# 01_MCU.net
KiCad netlist of a schematic drawn in Altium Designer
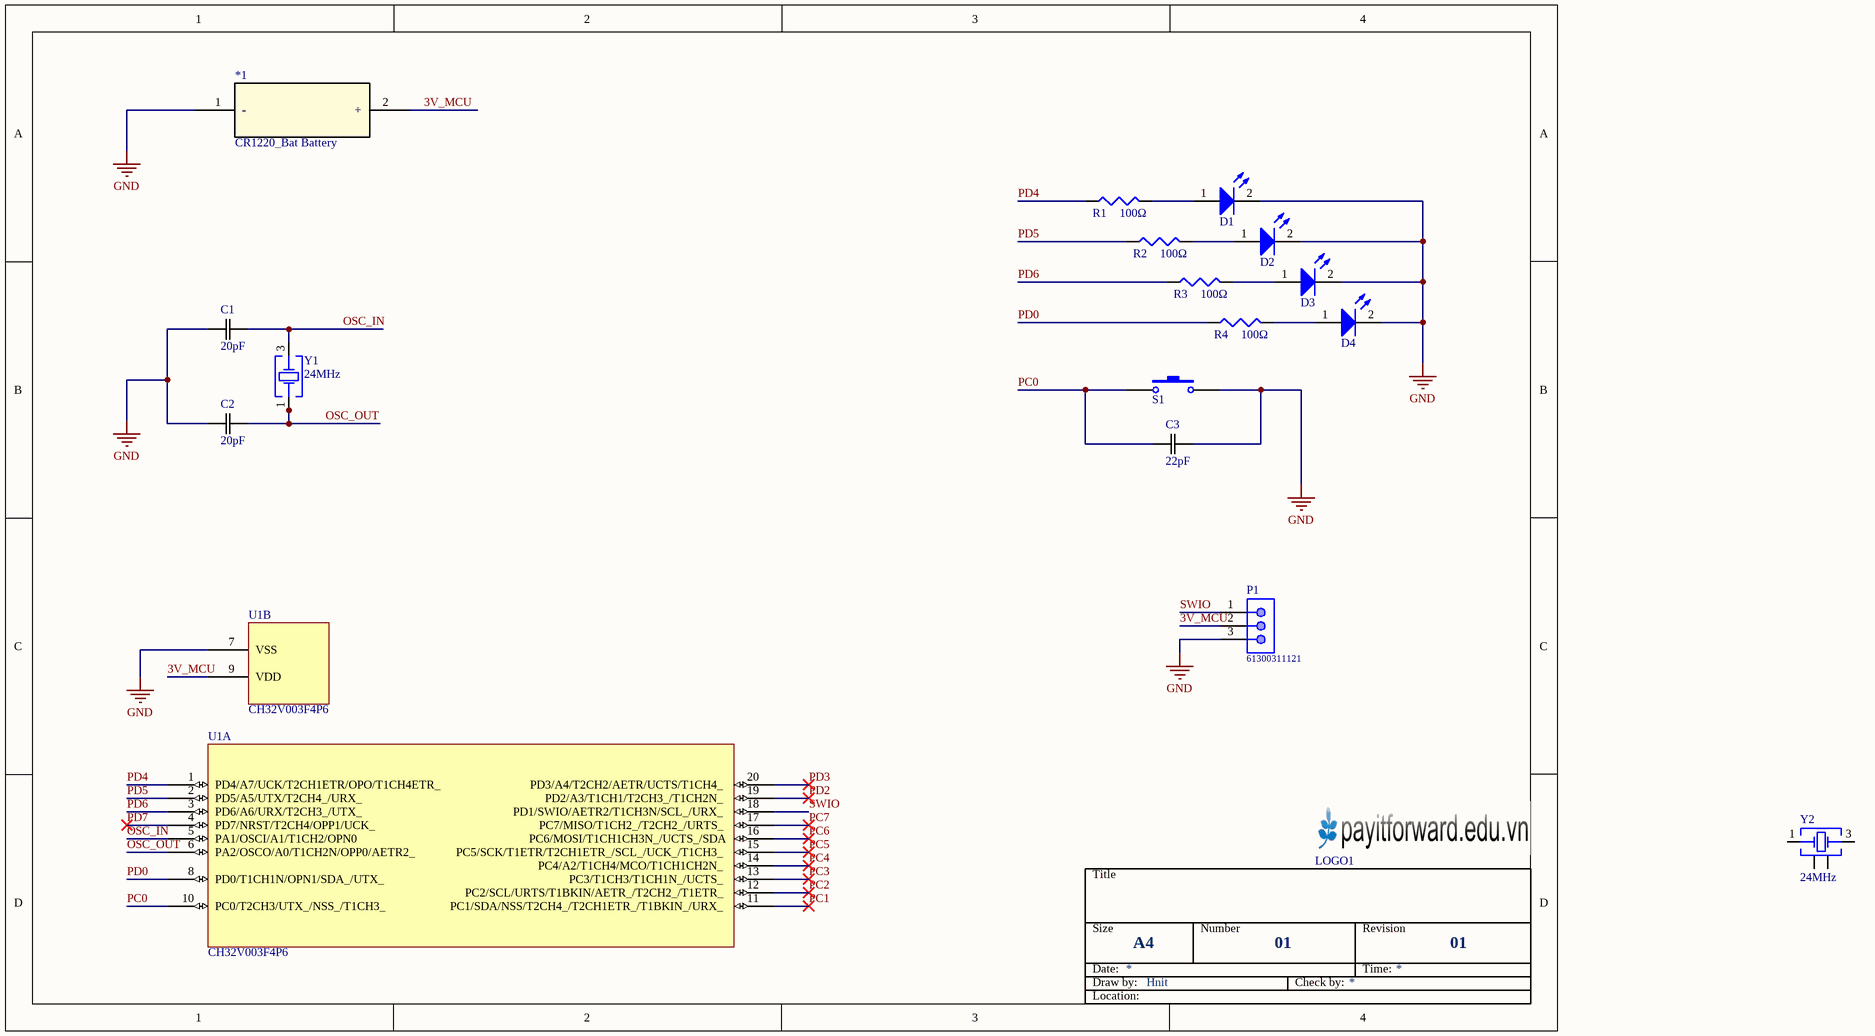
[diagram p0: 01_MCU.SchDoc]

(export (version "E")
  (design (tool "Eeschema 10.0.6"))
  (components
    (comp (ref "*1")
      (value "CR1220_Bat Battery")
      (footprint "CR1220_Bat Battery")
      (libsource (lib "IntegratedLibrary_Hnit") (part "CR1220_Bat Battery"))
    )
    (comp (ref "C1")
      (value "20pF")
      (footprint "CAPC17595_87N_KEM_0603")
      (description "No Description Available")
      (fields
        (field (name "MANUFACTURER_PART_NUMBER") "C1206C104K5RACTU")
        (field (name "COPYRIGHT") "Copyright (C) 2023 Ultra Librarian. All rights reserved.")
      )
      (libsource (lib "IntegratedLibrary_Hnit") (part "Capacitor_SMD"))
    )
    (comp (ref "C2")
      (value "20pF")
      (footprint "CAPC17595_87N_KEM_0603")
      (description "No Description Available")
      (fields
        (field (name "MANUFACTURER_PART_NUMBER") "C1206C104K5RACTU")
        (field (name "COPYRIGHT") "Copyright (C) 2023 Ultra Librarian. All rights reserved.")
      )
      (libsource (lib "IntegratedLibrary_Hnit") (part "Capacitor_SMD"))
    )
    (comp (ref "C3")
      (value "22pF")
      (footprint "CAPC17595_87N_KEM_0603")
      (description "No Description Available")
      (fields
        (field (name "MANUFACTURER_PART_NUMBER") "C1206C104K5RACTU")
        (field (name "COPYRIGHT") "Copyright (C) 2023 Ultra Librarian. All rights reserved.")
      )
      (libsource (lib "IntegratedLibrary_Hnit") (part "Capacitor_SMD"))
    )
    (comp (ref "D1")
      (value "Color ? , 3.2V, 140°")
      (footprint "WL-SMCW_0603_150060xx75003")
      (description "WL-SMCW Mono-color Chip LED Waterclear, size ?, color ?, 3.2V, 140°")
      (fields
        (field (name "MANUFACTURER PART NUMBER") "150060BS75003")
        (field (name "MANUFACTURER") "Wurth Elektronik")
      )
      (libsource (lib "IntegratedLibrary_Hnit") (part "LED_smd"))
    )
    (comp (ref "D2")
      (value "Color ? , 3.2V, 140°")
      (footprint "WL-SMCW_0603_150060xx75003")
      (description "WL-SMCW Mono-color Chip LED Waterclear, size ?, color ?, 3.2V, 140°")
      (fields
        (field (name "MANUFACTURER PART NUMBER") "150060BS75003")
        (field (name "MANUFACTURER") "Wurth Elektronik")
      )
      (libsource (lib "IntegratedLibrary_Hnit") (part "LED_smd"))
    )
    (comp (ref "D3")
      (value "Color ? , 3.2V, 140°")
      (footprint "WL-SMCW_0603_150060xx75003")
      (description "WL-SMCW Mono-color Chip LED Waterclear, size ?, color ?, 3.2V, 140°")
      (fields
        (field (name "MANUFACTURER PART NUMBER") "150060BS75003")
        (field (name "MANUFACTURER") "Wurth Elektronik")
      )
      (libsource (lib "IntegratedLibrary_Hnit") (part "LED_smd"))
    )
    (comp (ref "D4")
      (value "Color ? , 3.2V, 140°")
      (footprint "WL-SMCW_0603_150060xx75003")
      (description "WL-SMCW Mono-color Chip LED Waterclear, size ?, color ?, 3.2V, 140°")
      (fields
        (field (name "MANUFACTURER PART NUMBER") "150060BS75003")
        (field (name "MANUFACTURER") "Wurth Elektronik")
      )
      (libsource (lib "IntegratedLibrary_Hnit") (part "LED_smd"))
    )
    (comp (ref "LOGO1")
      (value "LOGO PIF")
      (footprint "PIF LOGO BIG TOP")
      (libsource (lib "PIF_Library") (part "LOGO PIF"))
    )
    (comp (ref "P1")
      (value "61300311121")
      (footprint "61300311121")
      (description "WR-PHD Pin Header, THT, pitch 2.54mm, Single Row, Vertical, 3p")
      (fields (field (name "MANUFACTURER") "Wurth Elektronik"))
      (libsource (lib "Altium_WR-PHD (rev20a)") (part "61300311121"))
    )
    (comp (ref "R1")
      (value "100Ω")
      (footprint "WRIS-PSMB_0603_L1.6W0.8H0.3 - duplicate")
      (description "WRIS-PSMC Metal Plate Resistor, SMT, size 2512, 2W, 5mΩ, +/-1%")
      (fields
        (field (name "MANUFACTURER PART NUMBER") "580070763005")
        (field (name "MANUFACTURER") "Wurth Elektronik")
      )
      (libsource (lib "IntegratedLibrary_Hnit") (part "Resistor_SMD"))
    )
    (comp (ref "R2")
      (value "100Ω")
      (footprint "WRIS-PSMB_0603_L1.6W0.8H0.3 - duplicate")
      (description "WRIS-PSMC Metal Plate Resistor, SMT, size 2512, 2W, 5mΩ, +/-1%")
      (fields
        (field (name "MANUFACTURER PART NUMBER") "580070763005")
        (field (name "MANUFACTURER") "Wurth Elektronik")
      )
      (libsource (lib "IntegratedLibrary_Hnit") (part "Resistor_SMD"))
    )
    (comp (ref "R3")
      (value "100Ω")
      (footprint "WRIS-PSMB_0603_L1.6W0.8H0.3 - duplicate")
      (description "WRIS-PSMC Metal Plate Resistor, SMT, size 2512, 2W, 5mΩ, +/-1%")
      (fields
        (field (name "MANUFACTURER PART NUMBER") "580070763005")
        (field (name "MANUFACTURER") "Wurth Elektronik")
      )
      (libsource (lib "IntegratedLibrary_Hnit") (part "Resistor_SMD"))
    )
    (comp (ref "R4")
      (value "100Ω")
      (footprint "WRIS-PSMB_0603_L1.6W0.8H0.3 - duplicate")
      (description "WRIS-PSMC Metal Plate Resistor, SMT, size 2512, 2W, 5mΩ, +/-1%")
      (fields
        (field (name "MANUFACTURER PART NUMBER") "580070763005")
        (field (name "MANUFACTURER") "Wurth Elektronik")
      )
      (libsource (lib "IntegratedLibrary_Hnit") (part "Resistor_SMD"))
    )
    (comp (ref "S1")
      (value "Tact SW - 2Pin")
      (footprint "SW-SMD")
      (description "Switch button 2 pin")
      (libsource (lib "IntegratedLibrary_Hnit") (part "Tact SW - 2Pin"))
    )
    (comp (ref "U1")
      (value "CH32V003F4P6")
      (footprint "TSOP20_CH32V003")
      (fields
        (field (name "VENDOR CONFIGURATION WORD STORAGE, FACTORY-CURED AND UNMODIFIABLE BY USERS") "64B")
      )
      (libsource (lib "IntegratedLibrary_Hnit") (part "CH32V003F4P6"))
    )
    (comp (ref "Y1")
      (value "24MHz")
      (footprint "WE-XTAL_CFPX-5032_2Pin")
      (description "WE-XTAL Quartz Crystal, SMT, CFPX-104, 24MHz, +/-50ppm")
      (fields
        (field (name "MANUFACTURER PART NUMBER") "830032817")
        (field (name "MANUFACTURER") "Wurth Elektronik")
      )
      (libsource (lib "IntegratedLibrary_Hnit") (part "XTAL_SMD"))
    )
    (comp (ref "Y2")
      (value "24MHz")
      (footprint "WE-XTAL_CFPX-104")
      (description "WE-XTAL Quartz Crystal, SMT, CFPX-104, 24MHz, +/-50ppm")
      (fields
        (field (name "MANUFACTURER PART NUMBER") "830032817")
        (field (name "MANUFACTURER") "Wurth Elektronik")
      )
      (libsource (lib "") (part "XTAL_SMD_1"))
    )
  )
  (nets
    (net (code "1") (name "/3V_MCU") (class "Default")
      (node (ref "*1") (pin "2") (pinfunction "+_2") (pintype "passive"))
      (node (ref "P1") (pin "2") (pinfunction "2_2") (pintype "passive"))
      (node (ref "U1") (pin "9") (pinfunction "VDD_9") (pintype "power_in"))
    )
    (net (code "2") (name "/OSC_IN") (class "Default")
      (node (ref "C1") (pin "2") (pinfunction "2_2") (pintype "passive"))
      (node (ref "U1") (pin "5") (pinfunction "PA1/OSCI/A1/T1CH2/OPN0_5") (pintype "bidirectional"))
      (node (ref "Y1") (pin "3") (pinfunction "Crystal_3") (pintype "passive"))
    )
    (net (code "3") (name "/OSC_OUT") (class "Default")
      (node (ref "C2") (pin "2") (pinfunction "2_2") (pintype "passive"))
      (node (ref "U1") (pin "6") (pinfunction "PA2/OSCO/A0/T1CH2N/OPP0/AETR2__6") (pintype "bidirectional"))
      (node (ref "Y1") (pin "1") (pinfunction "Crystal_1") (pintype "passive"))
    )
    (net (code "4") (name "/PC0") (class "Default")
      (node (ref "C3") (pin "1") (pinfunction "1_1") (pintype "passive"))
      (node (ref "S1") (pin "1") (pinfunction "1_1") (pintype "passive"))
      (node (ref "U1") (pin "10") (pinfunction "PC0/T2CH3/UTX_/NSS_/T1CH3__10") (pintype "bidirectional"))
    )
    (net (code "5") (name "/PC1") (class "Default")
      (node (ref "U1") (pin "11") (pinfunction "PC1/SDA/NSS/T2CH4_/T2CH1ETR_/T1BKIN_/URX__11") (pintype "bidirectional+no_connect"))
    )
    (net (code "6") (name "/PC2") (class "Default")
      (node (ref "U1") (pin "12") (pinfunction "PC2/SCL/URTS/T1BKIN/AETR_/T2CH2_/T1ETR__12") (pintype "bidirectional+no_connect"))
    )
    (net (code "7") (name "/PC3") (class "Default")
      (node (ref "U1") (pin "13") (pinfunction "PC3/T1CH3/T1CH1N_/UCTS__13") (pintype "bidirectional+no_connect"))
    )
    (net (code "8") (name "/PC4") (class "Default")
      (node (ref "U1") (pin "14") (pinfunction "PC4/A2/T1CH4/MCO/T1CH1CH2N__14") (pintype "bidirectional+no_connect"))
    )
    (net (code "9") (name "/PC5") (class "Default")
      (node (ref "U1") (pin "15") (pinfunction "PC5/SCK/T1ETR/T2CH1ETR_/SCL_/UCK_/T1CH3__15") (pintype "bidirectional+no_connect"))
    )
    (net (code "10") (name "/PC6") (class "Default")
      (node (ref "U1") (pin "16") (pinfunction "PC6/MOSI/T1CH1CH3N_/UCTS_/SDA_16") (pintype "bidirectional+no_connect"))
    )
    (net (code "11") (name "/PC7") (class "Default")
      (node (ref "U1") (pin "17") (pinfunction "PC7/MISO/T1CH2_/T2CH2_/URTS__17") (pintype "bidirectional+no_connect"))
    )
    (net (code "12") (name "/PD0") (class "Default")
      (node (ref "R4") (pin "1") (pinfunction "1_1") (pintype "passive"))
      (node (ref "U1") (pin "8") (pinfunction "PD0/T1CH1N/OPN1/SDA_/UTX__8") (pintype "bidirectional"))
    )
    (net (code "13") (name "/PD2") (class "Default")
      (node (ref "U1") (pin "19") (pinfunction "PD2/A3/T1CH1/T2CH3_/T1CH2N__19") (pintype "bidirectional+no_connect"))
    )
    (net (code "14") (name "/PD3") (class "Default")
      (node (ref "U1") (pin "20") (pinfunction "PD3/A4/T2CH2/AETR/UCTS/T1CH4__20") (pintype "bidirectional+no_connect"))
    )
    (net (code "15") (name "/PD4") (class "Default")
      (node (ref "R1") (pin "1") (pinfunction "1_1") (pintype "passive"))
      (node (ref "U1") (pin "1") (pinfunction "PD4/A7/UCK/T2CH1ETR/OPO/T1CH4ETR__1") (pintype "bidirectional"))
    )
    (net (code "16") (name "/PD5") (class "Default")
      (node (ref "R2") (pin "1") (pinfunction "1_1") (pintype "passive"))
      (node (ref "U1") (pin "2") (pinfunction "PD5/A5/UTX/T2CH4_/URX__2") (pintype "bidirectional"))
    )
    (net (code "17") (name "/PD6") (class "Default")
      (node (ref "R3") (pin "1") (pinfunction "1_1") (pintype "passive"))
      (node (ref "U1") (pin "3") (pinfunction "PD6/A6/URX/T2CH3_/UTX__3") (pintype "bidirectional"))
    )
    (net (code "18") (name "/PD7") (class "Default")
      (node (ref "U1") (pin "4") (pinfunction "PD7/NRST/T2CH4/OPP1/UCK__4") (pintype "bidirectional+no_connect"))
    )
    (net (code "19") (name "/SWIO") (class "Default")
      (node (ref "P1") (pin "1") (pinfunction "1_1") (pintype "passive"))
      (node (ref "U1") (pin "18") (pinfunction "PD1/SWIO/AETR2/T1CH3N/SCL_/URX__18") (pintype "bidirectional"))
    )
    (net (code "20") (name "GND") (class "Default")
      (node (ref "*1") (pin "1") (pinfunction "-_1") (pintype "passive"))
      (node (ref "C1") (pin "1") (pinfunction "1_1") (pintype "passive"))
      (node (ref "C2") (pin "1") (pinfunction "1_1") (pintype "passive"))
      (node (ref "C3") (pin "2") (pinfunction "2_2") (pintype "passive"))
      (node (ref "D1") (pin "2") (pinfunction "K_2") (pintype "passive"))
      (node (ref "D2") (pin "2") (pinfunction "K_2") (pintype "passive"))
      (node (ref "D3") (pin "2") (pinfunction "K_2") (pintype "passive"))
      (node (ref "D4") (pin "2") (pinfunction "K_2") (pintype "passive"))
      (node (ref "P1") (pin "3") (pinfunction "3_3") (pintype "passive"))
      (node (ref "S1") (pin "2") (pinfunction "2_2") (pintype "passive"))
      (node (ref "U1") (pin "7") (pinfunction "VSS_7") (pintype "power_in"))
    )
    (net (code "21") (name "Net-(D1-A)") (class "Default")
      (node (ref "D1") (pin "1") (pinfunction "A_1") (pintype "passive"))
      (node (ref "R1") (pin "2") (pinfunction "2_2") (pintype "passive"))
    )
    (net (code "22") (name "Net-(D2-A)") (class "Default")
      (node (ref "D2") (pin "1") (pinfunction "A_1") (pintype "passive"))
      (node (ref "R2") (pin "2") (pinfunction "2_2") (pintype "passive"))
    )
    (net (code "23") (name "Net-(D3-A)") (class "Default")
      (node (ref "D3") (pin "1") (pinfunction "A_1") (pintype "passive"))
      (node (ref "R3") (pin "2") (pinfunction "2_2") (pintype "passive"))
    )
    (net (code "24") (name "Net-(D4-A)") (class "Default")
      (node (ref "D4") (pin "1") (pinfunction "A_1") (pintype "passive"))
      (node (ref "R4") (pin "2") (pinfunction "2_2") (pintype "passive"))
    )
    (net (code "25") (name "unconnected-(Y2-Crystal-Pad1)") (class "Default")
      (node (ref "Y2") (pin "1") (pinfunction "Crystal_1") (pintype "passive"))
    )
    (net (code "26") (name "unconnected-(Y2-Crystal-Pad3)") (class "Default")
      (node (ref "Y2") (pin "3") (pinfunction "Crystal_3") (pintype "passive"))
    )
    (net (code "27") (name "unconnected-(Y2-GND_&_Lid-Pad2)") (class "Default")
      (node (ref "Y2") (pin "2") (pinfunction "GND_&_Lid_2") (pintype "passive"))
    )
    (net (code "28") (name "unconnected-(Y2-GND_&_Lid-Pad4)") (class "Default")
      (node (ref "Y2") (pin "4") (pinfunction "GND_&_Lid_4") (pintype "passive"))
    )
  )
)
